# ssr.net
KiCad netlist of a schematic drawn in EAGLE
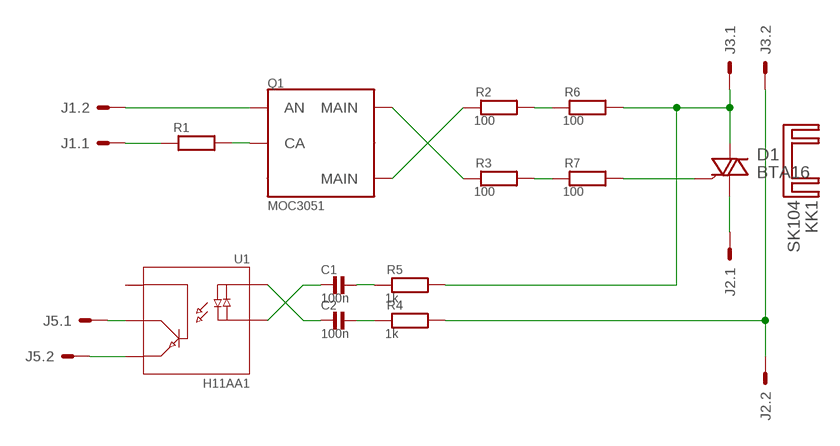
[diagram p0: schematic, sheet 1]

(export (version "E")
  (design (tool "Eeschema 10.0.6"))
  (components
    (comp (ref "C1")
      (value "100n")
      (footprint "eagle-import:_1206")
      (libsource (lib "eagle-import") (part "MLCC_1206"))
    )
    (comp (ref "C2")
      (value "100n")
      (footprint "eagle-import:_1206")
      (libsource (lib "eagle-import") (part "MLCC_1206"))
    )
    (comp (ref "D1")
      (value "BTA16")
      (footprint "eagle-import:TO220DS")
      (libsource (lib "eagle-import") (part "BTA16"))
    )
    (comp (ref "J1")
      (value "2EDG-2P")
      (footprint "eagle-import:2EDG-2P")
      (libsource (lib "eagle-import") (part "2EDG-2P"))
    )
    (comp (ref "J2")
      (value "2EDG-2P")
      (footprint "eagle-import:2EDG-2P")
      (libsource (lib "eagle-import") (part "2EDG-2P"))
    )
    (comp (ref "J3")
      (value "2EDG-2P")
      (footprint "eagle-import:2EDG-2P")
      (libsource (lib "eagle-import") (part "2EDG-2P"))
    )
    (comp (ref "J5")
      (value "2EDG-2P")
      (footprint "eagle-import:2EDG-2P")
      (libsource (lib "eagle-import") (part "2EDG-2P"))
    )
    (comp (ref "KK1")
      (value "SK104")
      (footprint "eagle-import:SK104")
      (libsource (lib "eagle-import") (part "SK104"))
    )
    (comp (ref "Q1")
      (value "MOC3051")
      (footprint "eagle-import:DIP-6-SMD")
      (libsource (lib "eagle-import") (part "MOC3051"))
    )
    (comp (ref "R1")
      (value "220")
      (footprint "eagle-import:0603_WAVE")
      (libsource (lib "eagle-import") (part "RESISTOR0603"))
    )
    (comp (ref "R2")
      (value "100")
      (footprint "eagle-import:_1206")
      (libsource (lib "eagle-import") (part "RESISTOR_1206"))
    )
    (comp (ref "R3")
      (value "100")
      (footprint "eagle-import:_1206")
      (libsource (lib "eagle-import") (part "RESISTOR_1206"))
    )
    (comp (ref "R4")
      (value "1k")
      (footprint "eagle-import:_1206")
      (libsource (lib "eagle-import") (part "RESISTOR_1206"))
    )
    (comp (ref "R5")
      (value "1k")
      (footprint "eagle-import:_1206")
      (libsource (lib "eagle-import") (part "RESISTOR_1206"))
    )
    (comp (ref "R6")
      (value "100")
      (footprint "eagle-import:_1206")
      (libsource (lib "eagle-import") (part "RESISTOR_1206"))
    )
    (comp (ref "R7")
      (value "100")
      (footprint "eagle-import:_1206")
      (libsource (lib "eagle-import") (part "RESISTOR_1206"))
    )
    (comp (ref "U1")
      (value "H11AA1")
      (footprint "eagle-import:DIP-6-SMD")
      (libsource (lib "eagle-import") (part "H11AA1"))
    )
  )
  (nets
    (net (code "1") (name "Net-(C1-P$1)") (class "Default")
      (node (ref "C1") (pin "1") (pinfunction "P$1_1") (pintype "bidirectional"))
      (node (ref "R5") (pin "1") (pinfunction "P$1_1") (pintype "bidirectional"))
    )
    (net (code "2") (name "Net-(C1-P$2)") (class "Default")
      (node (ref "C1") (pin "2") (pinfunction "P$2_2") (pintype "bidirectional"))
      (node (ref "U1") (pin "P$2") (pinfunction "CA_P$2") (pintype "bidirectional"))
    )
    (net (code "3") (name "Net-(C2-P$1)") (class "Default")
      (node (ref "C2") (pin "1") (pinfunction "P$1_1") (pintype "bidirectional"))
      (node (ref "R4") (pin "1") (pinfunction "P$1_1") (pintype "bidirectional"))
    )
    (net (code "4") (name "Net-(C2-P$2)") (class "Default")
      (node (ref "C2") (pin "2") (pinfunction "P$2_2") (pintype "bidirectional"))
      (node (ref "U1") (pin "P$1") (pinfunction "AC_P$1") (pintype "bidirectional"))
    )
    (net (code "5") (name "Net-(J1A-S)") (class "Default")
      (node (ref "J1") (pin "P$1") (pinfunction "S_P$1") (pintype "passive"))
      (node (ref "R1") (pin "P$1") (pinfunction "P$1_P$1") (pintype "bidirectional"))
    )
    (net (code "6") (name "Net-(J1B-S)") (class "Default")
      (node (ref "J1") (pin "P$2") (pinfunction "S_P$2") (pintype "passive"))
      (node (ref "Q1") (pin "P$1") (pinfunction "AN_P$1") (pintype "bidirectional"))
    )
    (net (code "7") (name "Net-(J2A-S)") (class "Default")
      (node (ref "D1") (pin "A1") (pinfunction "A1_A1") (pintype "passive"))
      (node (ref "J2") (pin "P$1") (pinfunction "S_P$1") (pintype "passive"))
    )
    (net (code "8") (name "Net-(J2B-S)") (class "Default")
      (node (ref "J2") (pin "P$2") (pinfunction "S_P$2") (pintype "passive"))
      (node (ref "J3") (pin "P$2") (pinfunction "S_P$2") (pintype "passive"))
      (node (ref "R4") (pin "2") (pinfunction "P$2_2") (pintype "bidirectional"))
    )
    (net (code "9") (name "Net-(J3A-S)") (class "Default")
      (node (ref "D1") (pin "A2") (pinfunction "A2_A2") (pintype "passive"))
      (node (ref "J3") (pin "P$1") (pinfunction "S_P$1") (pintype "passive"))
      (node (ref "R5") (pin "2") (pinfunction "P$2_2") (pintype "bidirectional"))
      (node (ref "R6") (pin "2") (pinfunction "P$2_2") (pintype "bidirectional"))
    )
    (net (code "10") (name "Net-(J5A-S)") (class "Default")
      (node (ref "J5") (pin "P$1") (pinfunction "S_P$1") (pintype "passive"))
      (node (ref "U1") (pin "P$5") (pinfunction "C_P$5") (pintype "bidirectional"))
    )
    (net (code "11") (name "Net-(J5B-S)") (class "Default")
      (node (ref "J5") (pin "P$2") (pinfunction "S_P$2") (pintype "passive"))
      (node (ref "U1") (pin "P$4") (pinfunction "E_P$4") (pintype "bidirectional"))
    )
    (net (code "12") (name "Net-(Q1-CA)") (class "Default")
      (node (ref "Q1") (pin "P$2") (pinfunction "CA_P$2") (pintype "bidirectional"))
      (node (ref "R1") (pin "P$2") (pinfunction "P$2_P$2") (pintype "bidirectional"))
    )
    (net (code "13") (name "Net-(R2-P$1)") (class "Default")
      (node (ref "Q1") (pin "P$6") (pinfunction "MAIN_P$6") (pintype "bidirectional"))
      (node (ref "R2") (pin "1") (pinfunction "P$1_1") (pintype "bidirectional"))
    )
    (net (code "14") (name "Net-(R2-P$2)") (class "Default")
      (node (ref "R2") (pin "2") (pinfunction "P$2_2") (pintype "bidirectional"))
      (node (ref "R6") (pin "1") (pinfunction "P$1_1") (pintype "bidirectional"))
    )
    (net (code "15") (name "Net-(R3-P$1)") (class "Default")
      (node (ref "Q1") (pin "P$4") (pinfunction "MAIN_P$4") (pintype "bidirectional"))
      (node (ref "R3") (pin "1") (pinfunction "P$1_1") (pintype "bidirectional"))
    )
    (net (code "16") (name "Net-(R3-P$2)") (class "Default")
      (node (ref "R3") (pin "2") (pinfunction "P$2_2") (pintype "bidirectional"))
      (node (ref "R7") (pin "1") (pinfunction "P$1_1") (pintype "bidirectional"))
    )
    (net (code "17") (name "Net-(R7-P$2)") (class "Default")
      (node (ref "D1") (pin "G") (pinfunction "G_G") (pintype "passive"))
      (node (ref "R7") (pin "2") (pinfunction "P$2_2") (pintype "bidirectional"))
    )
    (net (code "18") (name "unconnected-(U1-B-PadP$6)") (class "Default")
      (node (ref "U1") (pin "P$6") (pinfunction "B_P$6") (pintype "bidirectional"))
    )
  )
)
